# untitled.net
KiCad netlist of a schematic drawn in EAGLE
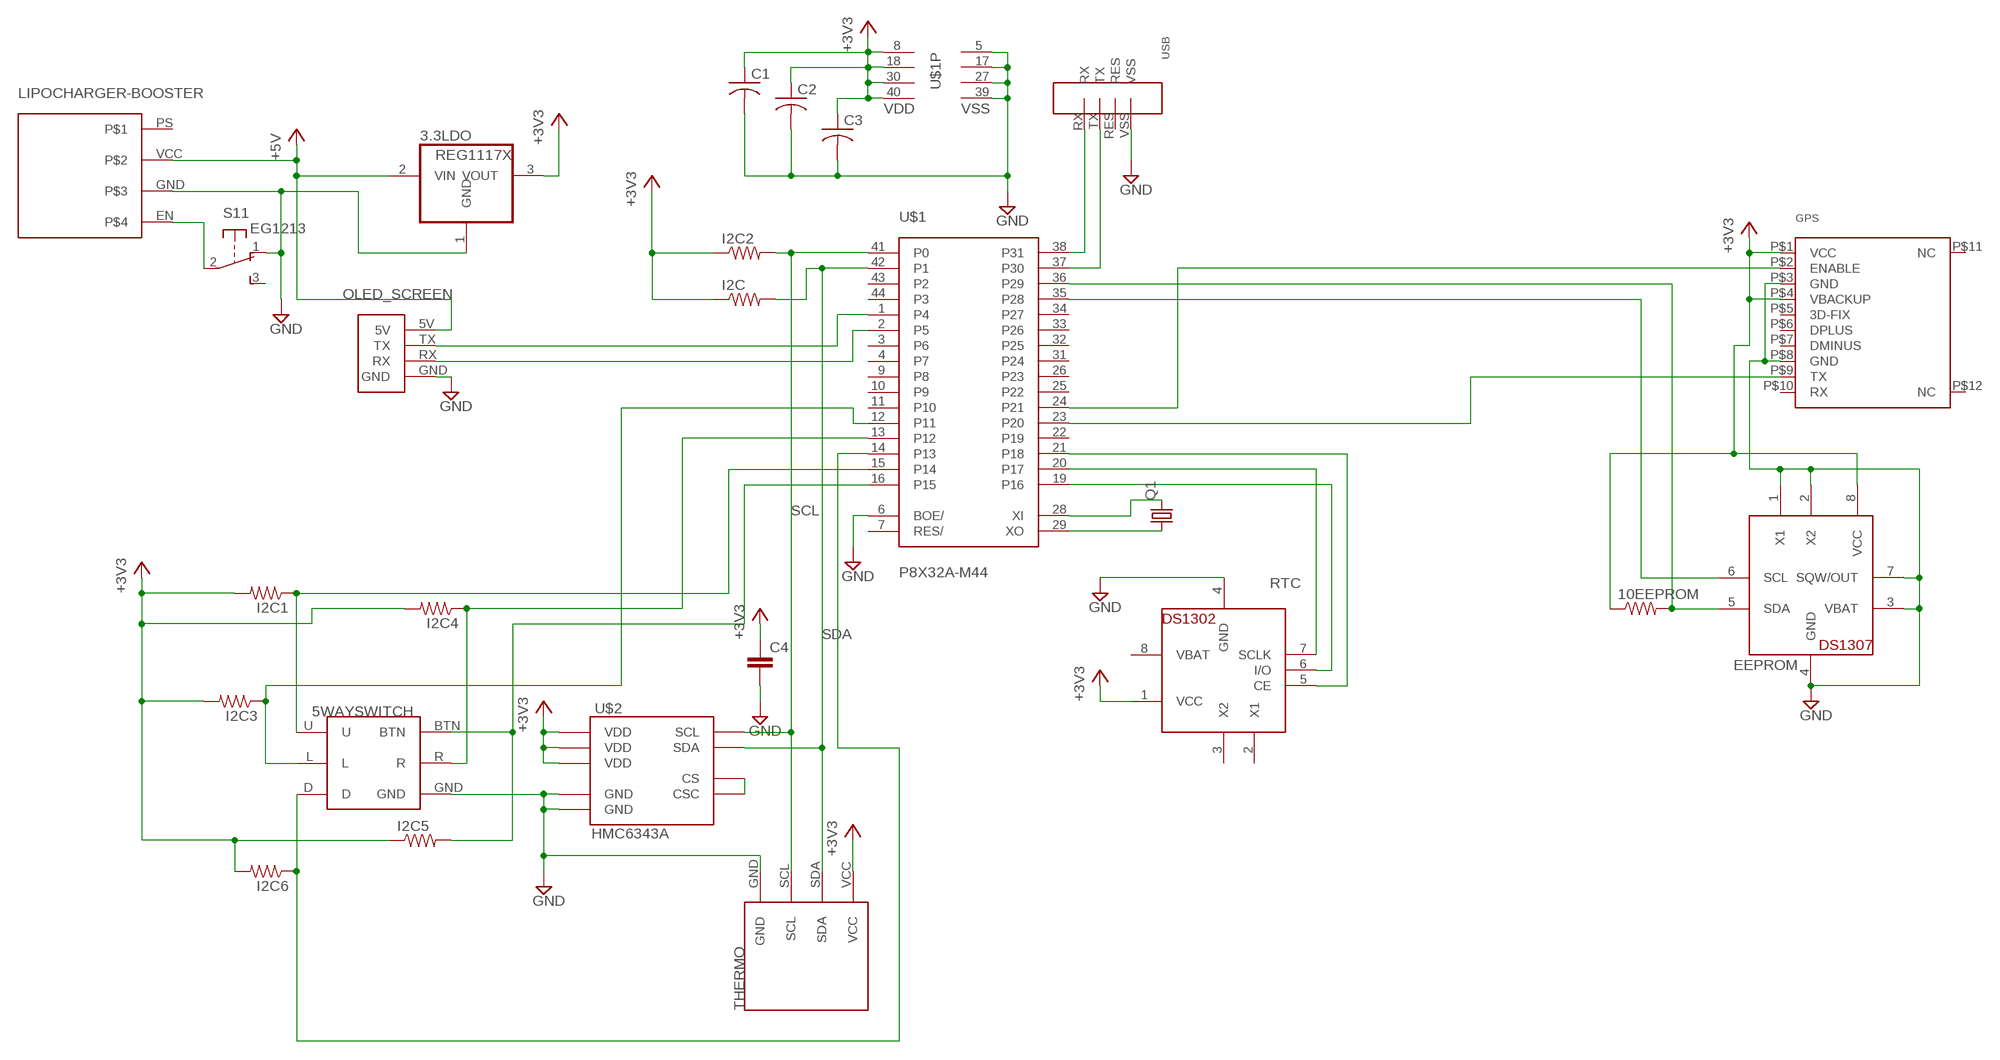
[diagram p0: schematic, sheet 1]

(export (version "E")
  (design (tool "Eeschema 10.0.6"))
  (components
    (comp (ref "3.3LDO")
      (value "REG1117X")
      (footprint "eagle-import:TO252")
      (libsource (lib "eagle-import") (part "REG1117X"))
    )
    (comp (ref "5WAYSWITCH")
      (value "5-WAYSWITCH")
      (footprint "eagle-import:5-WAYSWITCH")
      (libsource (lib "eagle-import") (part "5-WAYSWITCH"))
    )
    (comp (ref "10EEPROM")
      (value "R-US_R1005")
      (footprint "eagle-import:R1005")
      (libsource (lib "eagle-import") (part "R-US_R1005"))
    )
    (comp (ref "C1")
      (value "C-USC0603")
      (footprint "eagle-import:C0603")
      (libsource (lib "eagle-import") (part "C-USC0603"))
    )
    (comp (ref "C2")
      (value "C-USC0603")
      (footprint "eagle-import:C0603")
      (libsource (lib "eagle-import") (part "C-USC0603"))
    )
    (comp (ref "C3")
      (value "C-USC0603")
      (footprint "eagle-import:C0603")
      (libsource (lib "eagle-import") (part "C-USC0603"))
    )
    (comp (ref "C4")
      (value "CAP0603")
      (footprint "eagle-import:0603")
      (libsource (lib "eagle-import") (part "CAP0603"))
    )
    (comp (ref "EEPROM")
      (value "DS1307")
      (footprint "eagle-import:DIL08")
      (libsource (lib "eagle-import") (part "DS1307"))
    )
    (comp (ref "GPS")
      (value "GPS_FGPMMOPA6B")
      (footprint "eagle-import:FGPMMOPA6B")
      (libsource (lib "eagle-import") (part "GPS_FGPMMOPA6B"))
    )
    (comp (ref "I2C")
      (value "R-US_R1005")
      (footprint "eagle-import:R1005")
      (libsource (lib "eagle-import") (part "R-US_R1005"))
    )
    (comp (ref "I2C1")
      (value "R-US_R1005")
      (footprint "eagle-import:R1005")
      (libsource (lib "eagle-import") (part "R-US_R1005"))
    )
    (comp (ref "I2C2")
      (value "R-US_R1005")
      (footprint "eagle-import:R1005")
      (libsource (lib "eagle-import") (part "R-US_R1005"))
    )
    (comp (ref "I2C3")
      (value "R-US_R1005")
      (footprint "eagle-import:R1005")
      (libsource (lib "eagle-import") (part "R-US_R1005"))
    )
    (comp (ref "I2C4")
      (value "R-US_R1005")
      (footprint "eagle-import:R1005")
      (libsource (lib "eagle-import") (part "R-US_R1005"))
    )
    (comp (ref "I2C5")
      (value "R-US_R1005")
      (footprint "eagle-import:R1005")
      (libsource (lib "eagle-import") (part "R-US_R1005"))
    )
    (comp (ref "I2C6")
      (value "R-US_R1005")
      (footprint "eagle-import:R1005")
      (libsource (lib "eagle-import") (part "R-US_R1005"))
    )
    (comp (ref "LIPOCHARGER-BOOSTER")
      (value "SFLIPO")
      (footprint "eagle-import:SFLIPO")
      (libsource (lib "eagle-import") (part "SFLIPO"))
    )
    (comp (ref "OLED_SCREEN")
      (value "4DSCREEN")
      (footprint "eagle-import:4DSCREEN")
      (libsource (lib "eagle-import") (part "4DSCREEN"))
    )
    (comp (ref "Q1")
      (value "CRYSTALHC49S")
      (footprint "eagle-import:HC49_S")
      (libsource (lib "eagle-import") (part "CRYSTALHC49S"))
    )
    (comp (ref "RTC")
      (value "DS1302")
      (footprint "eagle-import:DIL08-ROUND")
      (libsource (lib "eagle-import") (part "DS1302"))
    )
    (comp (ref "S1")
      (value "EG1213")
      (footprint "eagle-import:EG1213")
      (libsource (lib "eagle-import") (part "EG1213"))
    )
    (comp (ref "THERMO")
      (value "SFTEMP")
      (footprint "eagle-import:SFTEMP")
      (libsource (lib "eagle-import") (part "SFTEMP"))
    )
    (comp (ref "U$1")
      (value "P8X32A-M44")
      (footprint "eagle-import:P8X32A-M44")
      (libsource (lib "eagle-import") (part "P8X32A-M44"))
    )
    (comp (ref "U$2")
      (value "HMC6343A")
      (footprint "eagle-import:LCC36")
      (libsource (lib "eagle-import") (part "HMC6343A"))
    )
    (comp (ref "USB")
      (value "4PINUSB")
      (footprint "eagle-import:4PINUSB")
      (libsource (lib "eagle-import") (part "4PINUSB"))
    )
  )
  (nets
    (net (code "1") (name "+3V3") (class "Default")
      (node (ref "10EEPROM") (pin "1") (pinfunction "1_1") (pintype "passive"))
      (node (ref "3.3LDO") (pin "3") (pinfunction "VOUT_3") (pintype "output"))
      (node (ref "C1") (pin "1") (pinfunction "1_1") (pintype "passive"))
      (node (ref "C2") (pin "1") (pinfunction "1_1") (pintype "passive"))
      (node (ref "C3") (pin "1") (pinfunction "1_1") (pintype "passive"))
      (node (ref "C4") (pin "1") (pinfunction "1_1") (pintype "passive"))
      (node (ref "EEPROM") (pin "8") (pinfunction "VCC_8") (pintype "power_in"))
      (node (ref "GPS") (pin "P$1") (pinfunction "VCC_P$1") (pintype "bidirectional"))
      (node (ref "GPS") (pin "P$4") (pinfunction "VBACKUP_P$4") (pintype "bidirectional"))
      (node (ref "I2C") (pin "1") (pinfunction "1_1") (pintype "passive"))
      (node (ref "I2C1") (pin "2") (pinfunction "2_2") (pintype "passive"))
      (node (ref "I2C2") (pin "1") (pinfunction "1_1") (pintype "passive"))
      (node (ref "I2C3") (pin "2") (pinfunction "2_2") (pintype "passive"))
      (node (ref "I2C4") (pin "2") (pinfunction "2_2") (pintype "passive"))
      (node (ref "I2C5") (pin "1") (pinfunction "1_1") (pintype "passive"))
      (node (ref "I2C6") (pin "2") (pinfunction "2_2") (pintype "passive"))
      (node (ref "RTC") (pin "1") (pinfunction "VCC_1") (pintype "power_in"))
      (node (ref "THERMO") (pin "VCC") (pinfunction "VCC_VCC") (pintype "bidirectional"))
      (node (ref "U$1") (pin "18") (pinfunction "VDD_18") (pintype "power_in"))
      (node (ref "U$1") (pin "30") (pinfunction "VDD_30") (pintype "power_in"))
      (node (ref "U$1") (pin "40") (pinfunction "VDD_40") (pintype "power_in"))
      (node (ref "U$1") (pin "8") (pinfunction "VDD_8") (pintype "power_in"))
      (node (ref "U$2") (pin "11") (pinfunction "VDD_11") (pintype "bidirectional"))
      (node (ref "U$2") (pin "21") (pinfunction "VDD_21") (pintype "bidirectional"))
      (node (ref "U$2") (pin "3") (pinfunction "VDD_3") (pintype "bidirectional"))
    )
    (net (code "2") (name "+5V") (class "Default")
      (node (ref "3.3LDO") (pin "2") (pinfunction "VIN_2") (pintype "input"))
      (node (ref "LIPOCHARGER-BOOSTER") (pin "VCC") (pinfunction "P$2_VCC") (pintype "bidirectional"))
      (node (ref "OLED_SCREEN") (pin "5V") (pinfunction "5V_5V") (pintype "bidirectional"))
    )
    (net (code "3") (name "/SCL") (class "Default")
      (node (ref "I2C2") (pin "2") (pinfunction "2_2") (pintype "passive"))
      (node (ref "THERMO") (pin "SCL") (pinfunction "SCL_SCL") (pintype "bidirectional"))
      (node (ref "U$1") (pin "41") (pinfunction "P0_41") (pintype "bidirectional"))
      (node (ref "U$2") (pin "32") (pinfunction "SCL_32") (pintype "bidirectional"))
    )
    (net (code "4") (name "/SDA") (class "Default")
      (node (ref "I2C") (pin "2") (pinfunction "2_2") (pintype "passive"))
      (node (ref "THERMO") (pin "SDA") (pinfunction "SDA_SDA") (pintype "bidirectional"))
      (node (ref "U$1") (pin "42") (pinfunction "P1_42") (pintype "bidirectional"))
      (node (ref "U$2") (pin "36") (pinfunction "SDA_36") (pintype "bidirectional"))
    )
    (net (code "5") (name "/VBAT") (class "Default")
      (node (ref "RTC") (pin "8") (pinfunction "VBAT_8") (pintype "power_in"))
    )
    (net (code "6") (name "GND") (class "Default")
      (node (ref "3.3LDO") (pin "1") (pinfunction "GND_1") (pintype "power_in"))
      (node (ref "5WAYSWITCH") (pin "GND") (pinfunction "GND_GND") (pintype "bidirectional"))
      (node (ref "C1") (pin "2") (pinfunction "2_2") (pintype "passive"))
      (node (ref "C2") (pin "2") (pinfunction "2_2") (pintype "passive"))
      (node (ref "C3") (pin "2") (pinfunction "2_2") (pintype "passive"))
      (node (ref "C4") (pin "2") (pinfunction "2_2") (pintype "passive"))
      (node (ref "EEPROM") (pin "1") (pinfunction "X1_1") (pintype "passive"))
      (node (ref "EEPROM") (pin "2") (pinfunction "X2_2") (pintype "passive"))
      (node (ref "EEPROM") (pin "3") (pinfunction "VBAT_3") (pintype "power_in"))
      (node (ref "EEPROM") (pin "4") (pinfunction "GND_4") (pintype "power_in"))
      (node (ref "EEPROM") (pin "7") (pinfunction "SQW/OUT_7") (pintype "bidirectional"))
      (node (ref "GPS") (pin "P$3") (pinfunction "GND_P$3") (pintype "bidirectional"))
      (node (ref "GPS") (pin "P$8") (pinfunction "GND_P$8") (pintype "bidirectional"))
      (node (ref "LIPOCHARGER-BOOSTER") (pin "GND") (pinfunction "P$3_GND") (pintype "bidirectional"))
      (node (ref "OLED_SCREEN") (pin "GND") (pinfunction "GND_GND") (pintype "bidirectional"))
      (node (ref "RTC") (pin "4") (pinfunction "GND_4") (pintype "power_in"))
      (node (ref "S1") (pin "1") (pinfunction "O_1") (pintype "passive"))
      (node (ref "THERMO") (pin "GND") (pinfunction "GND_GND") (pintype "bidirectional"))
      (node (ref "U$1") (pin "17") (pinfunction "VSS_17") (pintype "power_in"))
      (node (ref "U$1") (pin "27") (pinfunction "VSS_27") (pintype "power_in"))
      (node (ref "U$1") (pin "39") (pinfunction "VSS_39") (pintype "power_in"))
      (node (ref "U$1") (pin "5") (pinfunction "VSS_5") (pintype "power_in"))
      (node (ref "U$1") (pin "6") (pinfunction "BOE/_6") (pintype "input"))
      (node (ref "U$2") (pin "25") (pinfunction "GND_25") (pintype "bidirectional"))
      (node (ref "U$2") (pin "29") (pinfunction "GND_29") (pintype "bidirectional"))
      (node (ref "USB") (pin "VSS") (pinfunction "VSS_VSS") (pintype "bidirectional"))
    )
    (net (code "7") (name "Net-(EEPROM-SCL)") (class "Default")
      (node (ref "EEPROM") (pin "6") (pinfunction "SCL_6") (pintype "bidirectional"))
      (node (ref "U$1") (pin "35") (pinfunction "P28_35") (pintype "bidirectional"))
    )
    (net (code "8") (name "Net-(EEPROM-SDA)") (class "Default")
      (node (ref "10EEPROM") (pin "2") (pinfunction "2_2") (pintype "passive"))
      (node (ref "EEPROM") (pin "5") (pinfunction "SDA_5") (pintype "bidirectional"))
      (node (ref "U$1") (pin "36") (pinfunction "P29_36") (pintype "bidirectional"))
    )
    (net (code "9") (name "Net-(GPS-ENABLE)") (class "Default")
      (node (ref "GPS") (pin "P$2") (pinfunction "ENABLE_P$2") (pintype "bidirectional"))
      (node (ref "U$1") (pin "24") (pinfunction "P21_24") (pintype "bidirectional"))
    )
    (net (code "10") (name "Net-(GPS-TX)") (class "Default")
      (node (ref "GPS") (pin "P$9") (pinfunction "TX_P$9") (pintype "bidirectional"))
      (node (ref "U$1") (pin "23") (pinfunction "P20_23") (pintype "bidirectional"))
    )
    (net (code "11") (name "Net-(LIPOCHARGER-BOOSTER-P$4)") (class "Default")
      (node (ref "LIPOCHARGER-BOOSTER") (pin "EN") (pinfunction "P$4_EN") (pintype "bidirectional"))
      (node (ref "S1") (pin "2") (pinfunction "P_2") (pintype "passive"))
    )
    (net (code "12") (name "Net-(RTC-CE)") (class "Default")
      (node (ref "RTC") (pin "5") (pinfunction "CE_5") (pintype "input"))
      (node (ref "U$1") (pin "21") (pinfunction "P18_21") (pintype "bidirectional"))
    )
    (net (code "13") (name "Net-(RTC-I{slash}O)") (class "Default")
      (node (ref "RTC") (pin "6") (pinfunction "I/O_6") (pintype "bidirectional"))
      (node (ref "U$1") (pin "19") (pinfunction "P16_19") (pintype "bidirectional"))
    )
    (net (code "14") (name "Net-(RTC-SCLK)") (class "Default")
      (node (ref "RTC") (pin "7") (pinfunction "SCLK_7") (pintype "input"))
      (node (ref "U$1") (pin "20") (pinfunction "P17_20") (pintype "bidirectional"))
    )
    (net (code "15") (name "Net-(U$1A-P4)") (class "Default")
      (node (ref "OLED_SCREEN") (pin "TX") (pinfunction "TX_TX") (pintype "bidirectional"))
      (node (ref "U$1") (pin "1") (pinfunction "P4_1") (pintype "bidirectional"))
    )
    (net (code "16") (name "Net-(U$1A-P5)") (class "Default")
      (node (ref "OLED_SCREEN") (pin "RX") (pinfunction "RX_RX") (pintype "bidirectional"))
      (node (ref "U$1") (pin "2") (pinfunction "P5_2") (pintype "bidirectional"))
    )
    (net (code "17") (name "Net-(U$1A-P11)") (class "Default")
      (node (ref "5WAYSWITCH") (pin "L") (pinfunction "L_L") (pintype "bidirectional"))
      (node (ref "I2C3") (pin "1") (pinfunction "1_1") (pintype "passive"))
      (node (ref "U$1") (pin "12") (pinfunction "P11_12") (pintype "bidirectional"))
    )
    (net (code "18") (name "Net-(U$1A-P12)") (class "Default")
      (node (ref "5WAYSWITCH") (pin "R") (pinfunction "R_R") (pintype "bidirectional"))
      (node (ref "I2C4") (pin "1") (pinfunction "1_1") (pintype "passive"))
      (node (ref "U$1") (pin "13") (pinfunction "P12_13") (pintype "bidirectional"))
    )
    (net (code "19") (name "Net-(U$1A-P13)") (class "Default")
      (node (ref "5WAYSWITCH") (pin "D") (pinfunction "D_D") (pintype "bidirectional"))
      (node (ref "I2C6") (pin "1") (pinfunction "1_1") (pintype "passive"))
      (node (ref "U$1") (pin "14") (pinfunction "P13_14") (pintype "bidirectional"))
    )
    (net (code "20") (name "Net-(U$1A-P14)") (class "Default")
      (node (ref "5WAYSWITCH") (pin "U") (pinfunction "U_U") (pintype "bidirectional"))
      (node (ref "I2C1") (pin "1") (pinfunction "1_1") (pintype "passive"))
      (node (ref "U$1") (pin "15") (pinfunction "P14_15") (pintype "bidirectional"))
    )
    (net (code "21") (name "Net-(U$1A-P15)") (class "Default")
      (node (ref "5WAYSWITCH") (pin "BTN") (pinfunction "BTN_BTN") (pintype "bidirectional"))
      (node (ref "I2C5") (pin "2") (pinfunction "2_2") (pintype "passive"))
      (node (ref "U$1") (pin "16") (pinfunction "P15_16") (pintype "bidirectional"))
    )
    (net (code "22") (name "Net-(U$1A-P30)") (class "Default")
      (node (ref "U$1") (pin "37") (pinfunction "P30_37") (pintype "bidirectional"))
      (node (ref "USB") (pin "TX") (pinfunction "TX_TX") (pintype "bidirectional"))
    )
    (net (code "23") (name "Net-(U$1A-P31)") (class "Default")
      (node (ref "U$1") (pin "38") (pinfunction "P31_38") (pintype "bidirectional"))
      (node (ref "USB") (pin "RX") (pinfunction "RX_RX") (pintype "bidirectional"))
    )
    (net (code "24") (name "Net-(U$1A-XI)") (class "Default")
      (node (ref "Q1") (pin "2") (pinfunction "2_2") (pintype "passive"))
      (node (ref "U$1") (pin "28") (pinfunction "XI_28") (pintype "input"))
    )
    (net (code "25") (name "Net-(U$1A-XO)") (class "Default")
      (node (ref "Q1") (pin "1") (pinfunction "1_1") (pintype "passive"))
      (node (ref "U$1") (pin "29") (pinfunction "XO_29") (pintype "output"))
    )
    (net (code "26") (name "Net-(U$2-CS)") (class "Default")
      (node (ref "U$2") (pin "22") (pinfunction "CS_22") (pintype "bidirectional"))
      (node (ref "U$2") (pin "35") (pinfunction "CSC_35") (pintype "bidirectional"))
    )
    (net (code "27") (name "unconnected-(GPS-3D-FIX-PadP$5)") (class "Default")
      (node (ref "GPS") (pin "P$5") (pinfunction "3D-FIX_P$5") (pintype "bidirectional"))
    )
    (net (code "28") (name "unconnected-(GPS-DMINUS-PadP$7)") (class "Default")
      (node (ref "GPS") (pin "P$7") (pinfunction "DMINUS_P$7") (pintype "bidirectional"))
    )
    (net (code "29") (name "unconnected-(GPS-DPLUS-PadP$6)") (class "Default")
      (node (ref "GPS") (pin "P$6") (pinfunction "DPLUS_P$6") (pintype "bidirectional"))
    )
    (net (code "30") (name "unconnected-(GPS-NC-PadP$11)") (class "Default")
      (node (ref "GPS") (pin "P$11") (pinfunction "NC_P$11") (pintype "bidirectional"))
    )
    (net (code "31") (name "unconnected-(GPS-NC-PadP$12)") (class "Default")
      (node (ref "GPS") (pin "P$12") (pinfunction "NC_P$12") (pintype "bidirectional"))
    )
    (net (code "32") (name "unconnected-(GPS-RX-PadP$10)") (class "Default")
      (node (ref "GPS") (pin "P$10") (pinfunction "RX_P$10") (pintype "bidirectional"))
    )
    (net (code "33") (name "unconnected-(LIPOCHARGER-BOOSTER-P$1-PadPS)") (class "Default")
      (node (ref "LIPOCHARGER-BOOSTER") (pin "PS") (pinfunction "P$1_PS") (pintype "bidirectional"))
    )
    (net (code "34") (name "unconnected-(RTC-X1-Pad2)") (class "Default")
      (node (ref "RTC") (pin "2") (pinfunction "X1_2") (pintype "passive"))
    )
    (net (code "35") (name "unconnected-(RTC-X2-Pad3)") (class "Default")
      (node (ref "RTC") (pin "3") (pinfunction "X2_3") (pintype "passive"))
    )
    (net (code "36") (name "unconnected-(S1A-S-Pad3)") (class "Default")
      (node (ref "S1") (pin "3") (pinfunction "S_3") (pintype "passive"))
    )
    (net (code "37") (name "unconnected-(U$1A-P2-Pad43)") (class "Default")
      (node (ref "U$1") (pin "43") (pinfunction "P2_43") (pintype "bidirectional"))
    )
    (net (code "38") (name "unconnected-(U$1A-P3-Pad44)") (class "Default")
      (node (ref "U$1") (pin "44") (pinfunction "P3_44") (pintype "bidirectional"))
    )
    (net (code "39") (name "unconnected-(U$1A-P6-Pad3)") (class "Default")
      (node (ref "U$1") (pin "3") (pinfunction "P6_3") (pintype "bidirectional"))
    )
    (net (code "40") (name "unconnected-(U$1A-P7-Pad4)") (class "Default")
      (node (ref "U$1") (pin "4") (pinfunction "P7_4") (pintype "bidirectional"))
    )
    (net (code "41") (name "unconnected-(U$1A-P8-Pad9)") (class "Default")
      (node (ref "U$1") (pin "9") (pinfunction "P8_9") (pintype "bidirectional"))
    )
    (net (code "42") (name "unconnected-(U$1A-P9-Pad10)") (class "Default")
      (node (ref "U$1") (pin "10") (pinfunction "P9_10") (pintype "bidirectional"))
    )
    (net (code "43") (name "unconnected-(U$1A-P10-Pad11)") (class "Default")
      (node (ref "U$1") (pin "11") (pinfunction "P10_11") (pintype "bidirectional"))
    )
    (net (code "44") (name "unconnected-(U$1A-P19-Pad22)") (class "Default")
      (node (ref "U$1") (pin "22") (pinfunction "P19_22") (pintype "bidirectional"))
    )
    (net (code "45") (name "unconnected-(U$1A-P22-Pad25)") (class "Default")
      (node (ref "U$1") (pin "25") (pinfunction "P22_25") (pintype "bidirectional"))
    )
    (net (code "46") (name "unconnected-(U$1A-P23-Pad26)") (class "Default")
      (node (ref "U$1") (pin "26") (pinfunction "P23_26") (pintype "bidirectional"))
    )
    (net (code "47") (name "unconnected-(U$1A-P24-Pad31)") (class "Default")
      (node (ref "U$1") (pin "31") (pinfunction "P24_31") (pintype "bidirectional"))
    )
    (net (code "48") (name "unconnected-(U$1A-P25-Pad32)") (class "Default")
      (node (ref "U$1") (pin "32") (pinfunction "P25_32") (pintype "bidirectional"))
    )
    (net (code "49") (name "unconnected-(U$1A-P26-Pad33)") (class "Default")
      (node (ref "U$1") (pin "33") (pinfunction "P26_33") (pintype "bidirectional"))
    )
    (net (code "50") (name "unconnected-(U$1A-P27-Pad34)") (class "Default")
      (node (ref "U$1") (pin "34") (pinfunction "P27_34") (pintype "bidirectional"))
    )
    (net (code "51") (name "unconnected-(U$1A-RES{slash}-Pad7)") (class "Default")
      (node (ref "U$1") (pin "7") (pinfunction "RES/_7") (pintype "bidirectional"))
    )
    (net (code "52") (name "unconnected-(USB-PadRES)") (class "Default")
      (node (ref "USB") (pin "RES") (pinfunction "RES_RES") (pintype "bidirectional"))
    )
  )
)
